# Updated_Schematic_11-20.net
KiCad netlist of a schematic drawn in EAGLE
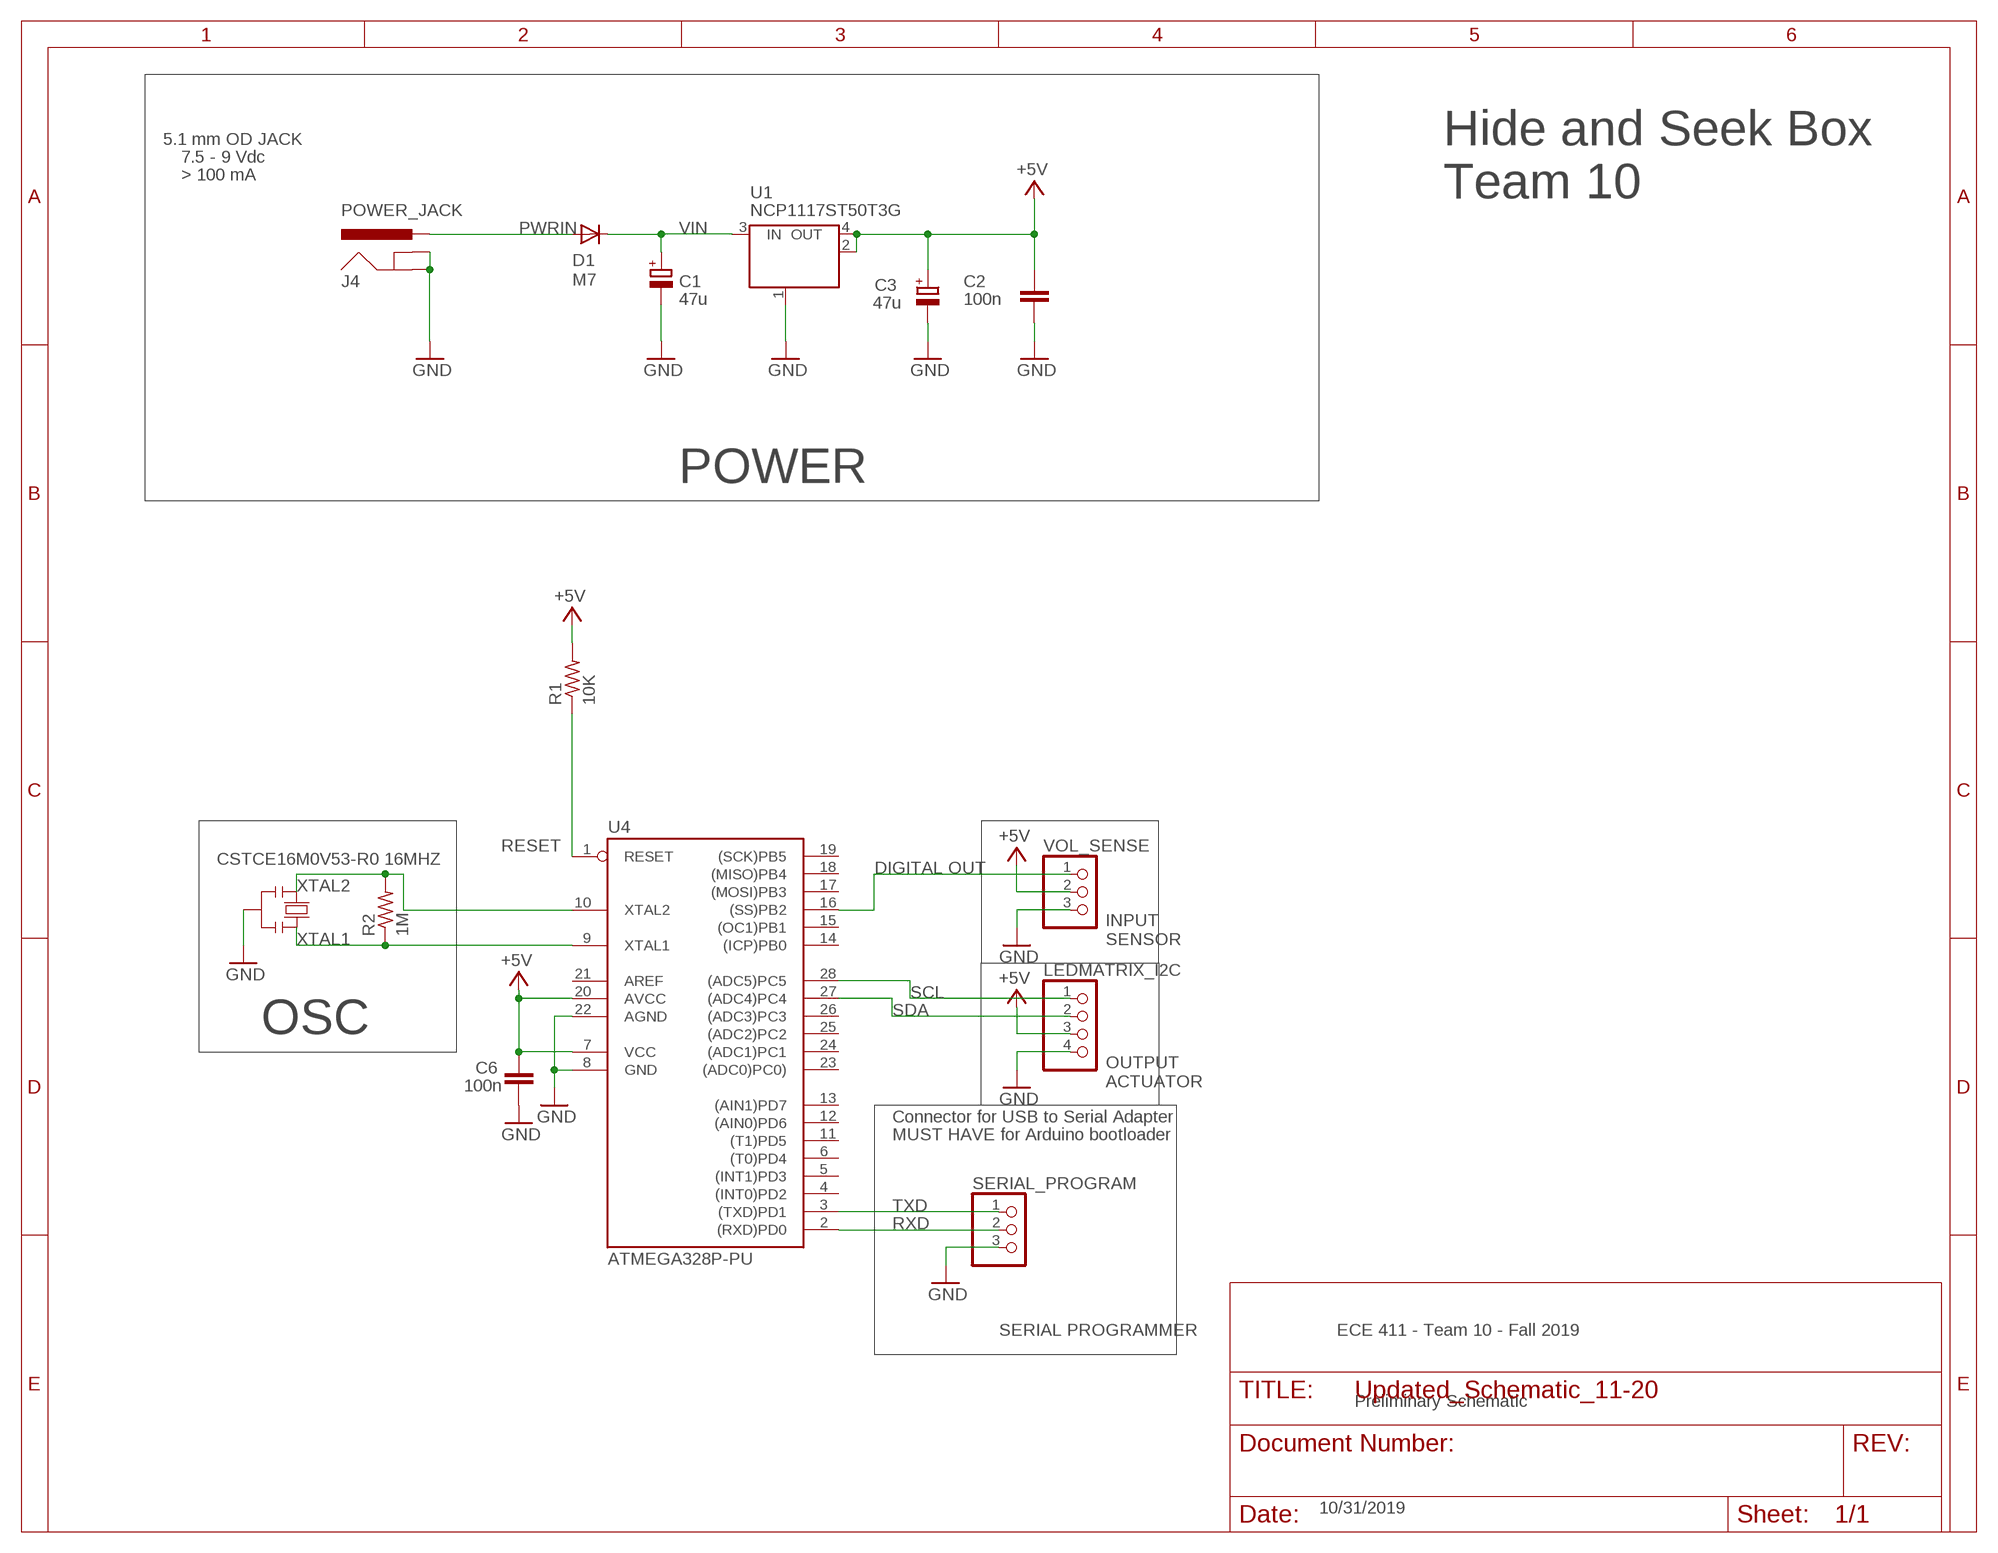
[diagram p0: schematic, sheet 1]

(export (version "E")
  (design (tool "Eeschema 10.0.6"))
  (components
    (comp (ref "C1")
      (value "47u")
      (footprint "eagle-import:PANASONIC_D")
      (libsource (lib "eagle-import") (part "CPOL-EUD"))
    )
    (comp (ref "C2")
      (value "100n")
      (footprint "eagle-import:C0805")
      (libsource (lib "eagle-import") (part "C-EUC0805"))
    )
    (comp (ref "C3")
      (value "47u")
      (footprint "eagle-import:PANASONIC_D")
      (libsource (lib "eagle-import") (part "CPOL-EUD"))
    )
    (comp (ref "C6")
      (value "100n")
      (footprint "eagle-import:C0805")
      (libsource (lib "eagle-import") (part "C-EUC0805"))
    )
    (comp (ref "D1")
      (value "M7")
      (footprint "eagle-import:SMB")
      (libsource (lib "eagle-import") (part "DIODE-SMB"))
    )
    (comp (ref "J4")
      (value "POWER_JACK")
      (footprint "eagle-import:POWER_JACK_PTH")
      (libsource (lib "eagle-import") (part "POWER_JACK"))
    )
    (comp (ref "LEDMATRIX_I2C")
      (value "PINHD-1X4")
      (footprint "eagle-import:1X04")
      (libsource (lib "eagle-import") (part "PINHD-1X4"))
    )
    (comp (ref "R1")
      (value "10K")
      (footprint "eagle-import:R0805")
      (libsource (lib "eagle-import") (part "R-US_R0805"))
    )
    (comp (ref "R2")
      (value "1M")
      (footprint "eagle-import:R0805")
      (libsource (lib "eagle-import") (part "R-US_R0805"))
    )
    (comp (ref "SERIAL_PROGRAM")
      (value "PINHD-1X3")
      (footprint "eagle-import:1X03")
      (libsource (lib "eagle-import") (part "PINHD-1X3"))
    )
    (comp (ref "U1")
      (value "NCP1117ST50T3G")
      (footprint "eagle-import:SOT223")
      (libsource (lib "eagle-import") (part "MC33269ST-3.3T3"))
    )
    (comp (ref "U4")
      (value "ATMEGA328P-PU")
      (footprint "eagle-import:DIL28-3")
      (libsource (lib "eagle-import") (part "ATMEGA328P-PU"))
    )
    (comp (ref "VOL_SENSE")
      (value "PINHD-1X3")
      (footprint "eagle-import:1X03")
      (libsource (lib "eagle-import") (part "PINHD-1X3"))
    )
    (comp (ref "X1")
      (value "CSTCE16M0V53-R0 16MHZ")
      (footprint "eagle-import:RESONATOR")
      (libsource (lib "eagle-import") (part "RESONATORMU"))
    )
  )
  (nets
    (net (code "1") (name "+5V") (class "Default")
      (node (ref "C2") (pin "2") (pinfunction "2_2") (pintype "passive"))
      (node (ref "C3") (pin "+") (pinfunction "+_+") (pintype "passive"))
      (node (ref "C6") (pin "2") (pinfunction "2_2") (pintype "passive"))
      (node (ref "LEDMATRIX_I2C") (pin "3") (pinfunction "3_3") (pintype "passive"))
      (node (ref "R1") (pin "2") (pinfunction "2_2") (pintype "passive"))
      (node (ref "U1") (pin "2") (pinfunction "OUT_2") (pintype "passive"))
      (node (ref "U1") (pin "4") (pinfunction "OUT_4") (pintype "passive"))
      (node (ref "U4") (pin "20") (pinfunction "AVCC_20") (pintype "power_in"))
      (node (ref "U4") (pin "7") (pinfunction "VCC_7") (pintype "power_in"))
      (node (ref "VOL_SENSE") (pin "2") (pinfunction "2_2") (pintype "passive"))
    )
    (net (code "2") (name "/PWRIN") (class "Default")
      (node (ref "D1") (pin "A") (pinfunction "A_A") (pintype "passive"))
      (node (ref "J4") (pin "PWR") (pinfunction "PWR_PWR") (pintype "bidirectional"))
    )
    (net (code "3") (name "/RESET") (class "Default")
      (node (ref "R1") (pin "1") (pinfunction "1_1") (pintype "passive"))
      (node (ref "U4") (pin "1") (pinfunction "RESET_1") (pintype "input"))
    )
    (net (code "4") (name "/RXD") (class "Default")
      (node (ref "SERIAL_PROGRAM") (pin "2") (pinfunction "2_2") (pintype "passive"))
      (node (ref "U4") (pin "2") (pinfunction "(RXD)PD0_2") (pintype "bidirectional"))
    )
    (net (code "5") (name "/SCL") (class "Default")
      (node (ref "LEDMATRIX_I2C") (pin "1") (pinfunction "1_1") (pintype "passive"))
      (node (ref "U4") (pin "28") (pinfunction "(ADC5)PC5_28") (pintype "bidirectional"))
    )
    (net (code "6") (name "/SDA") (class "Default")
      (node (ref "LEDMATRIX_I2C") (pin "2") (pinfunction "2_2") (pintype "passive"))
      (node (ref "U4") (pin "27") (pinfunction "(ADC4)PC4_27") (pintype "bidirectional"))
    )
    (net (code "7") (name "/TXD") (class "Default")
      (node (ref "SERIAL_PROGRAM") (pin "1") (pinfunction "1_1") (pintype "passive"))
      (node (ref "U4") (pin "3") (pinfunction "(TXD)PD1_3") (pintype "bidirectional"))
    )
    (net (code "8") (name "/VIN") (class "Default")
      (node (ref "C1") (pin "+") (pinfunction "+_+") (pintype "passive"))
      (node (ref "D1") (pin "C") (pinfunction "C_C") (pintype "passive"))
      (node (ref "U1") (pin "3") (pinfunction "IN_3") (pintype "input"))
    )
    (net (code "9") (name "/XTAL1") (class "Default")
      (node (ref "R2") (pin "1") (pinfunction "1_1") (pintype "passive"))
      (node (ref "U4") (pin "9") (pinfunction "XTAL1_9") (pintype "bidirectional"))
      (node (ref "X1") (pin "3") (pinfunction "3_3") (pintype "passive"))
    )
    (net (code "10") (name "/XTAL2") (class "Default")
      (node (ref "R2") (pin "2") (pinfunction "2_2") (pintype "passive"))
      (node (ref "U4") (pin "10") (pinfunction "XTAL2_10") (pintype "bidirectional"))
      (node (ref "X1") (pin "1") (pinfunction "1_1") (pintype "passive"))
    )
    (net (code "11") (name "GND") (class "Default")
      (node (ref "C1") (pin "-") (pinfunction "-_-") (pintype "passive"))
      (node (ref "C2") (pin "1") (pinfunction "1_1") (pintype "passive"))
      (node (ref "C3") (pin "-") (pinfunction "-_-") (pintype "passive"))
      (node (ref "C6") (pin "1") (pinfunction "1_1") (pintype "passive"))
      (node (ref "J4") (pin "GND") (pinfunction "GND_GND") (pintype "bidirectional"))
      (node (ref "J4") (pin "GNDBREAK") (pinfunction "GNDBREAK_GNDBREAK") (pintype "bidirectional"))
      (node (ref "LEDMATRIX_I2C") (pin "4") (pinfunction "4_4") (pintype "passive"))
      (node (ref "SERIAL_PROGRAM") (pin "3") (pinfunction "3_3") (pintype "passive"))
      (node (ref "U1") (pin "1") (pinfunction "GND/ADJ_1") (pintype "input"))
      (node (ref "U4") (pin "22") (pinfunction "AGND_22") (pintype "power_in"))
      (node (ref "U4") (pin "8") (pinfunction "GND_8") (pintype "power_in"))
      (node (ref "VOL_SENSE") (pin "3") (pinfunction "3_3") (pintype "passive"))
      (node (ref "X1") (pin "2") (pinfunction "2_2") (pintype "passive"))
    )
    (net (code "12") (name "Net-(U4-(SS)PB2)") (class "Default")
      (node (ref "U4") (pin "16") (pinfunction "(SS)PB2_16") (pintype "bidirectional"))
      (node (ref "VOL_SENSE") (pin "1") (pinfunction "1_1") (pintype "passive"))
    )
    (net (code "13") (name "unconnected-(U4-(ADC0)PC0)-Pad23)") (class "Default")
      (node (ref "U4") (pin "23") (pinfunction "(ADC0)PC0)_23") (pintype "bidirectional"))
    )
    (net (code "14") (name "unconnected-(U4-(ADC1)PC1-Pad24)") (class "Default")
      (node (ref "U4") (pin "24") (pinfunction "(ADC1)PC1_24") (pintype "bidirectional"))
    )
    (net (code "15") (name "unconnected-(U4-(ADC2)PC2-Pad25)") (class "Default")
      (node (ref "U4") (pin "25") (pinfunction "(ADC2)PC2_25") (pintype "bidirectional"))
    )
    (net (code "16") (name "unconnected-(U4-(ADC3)PC3-Pad26)") (class "Default")
      (node (ref "U4") (pin "26") (pinfunction "(ADC3)PC3_26") (pintype "bidirectional"))
    )
    (net (code "17") (name "unconnected-(U4-(AIN0)PD6-Pad12)") (class "Default")
      (node (ref "U4") (pin "12") (pinfunction "(AIN0)PD6_12") (pintype "bidirectional"))
    )
    (net (code "18") (name "unconnected-(U4-(AIN1)PD7-Pad13)") (class "Default")
      (node (ref "U4") (pin "13") (pinfunction "(AIN1)PD7_13") (pintype "bidirectional"))
    )
    (net (code "19") (name "unconnected-(U4-(ICP)PB0-Pad14)") (class "Default")
      (node (ref "U4") (pin "14") (pinfunction "(ICP)PB0_14") (pintype "bidirectional"))
    )
    (net (code "20") (name "unconnected-(U4-(INT0)PD2-Pad4)") (class "Default")
      (node (ref "U4") (pin "4") (pinfunction "(INT0)PD2_4") (pintype "bidirectional"))
    )
    (net (code "21") (name "unconnected-(U4-(INT1)PD3-Pad5)") (class "Default")
      (node (ref "U4") (pin "5") (pinfunction "(INT1)PD3_5") (pintype "bidirectional"))
    )
    (net (code "22") (name "unconnected-(U4-(MISO)PB4-Pad18)") (class "Default")
      (node (ref "U4") (pin "18") (pinfunction "(MISO)PB4_18") (pintype "bidirectional"))
    )
    (net (code "23") (name "unconnected-(U4-(MOSI)PB3-Pad17)") (class "Default")
      (node (ref "U4") (pin "17") (pinfunction "(MOSI)PB3_17") (pintype "bidirectional"))
    )
    (net (code "24") (name "unconnected-(U4-(OC1)PB1-Pad15)") (class "Default")
      (node (ref "U4") (pin "15") (pinfunction "(OC1)PB1_15") (pintype "bidirectional"))
    )
    (net (code "25") (name "unconnected-(U4-(SCK)PB5-Pad19)") (class "Default")
      (node (ref "U4") (pin "19") (pinfunction "(SCK)PB5_19") (pintype "bidirectional"))
    )
    (net (code "26") (name "unconnected-(U4-(T0)PD4-Pad6)") (class "Default")
      (node (ref "U4") (pin "6") (pinfunction "(T0)PD4_6") (pintype "bidirectional"))
    )
    (net (code "27") (name "unconnected-(U4-(T1)PD5-Pad11)") (class "Default")
      (node (ref "U4") (pin "11") (pinfunction "(T1)PD5_11") (pintype "bidirectional"))
    )
    (net (code "28") (name "unconnected-(U4-AREF-Pad21)") (class "Default")
      (node (ref "U4") (pin "21") (pinfunction "AREF_21") (pintype "passive"))
    )
  )
)
